# LED_STATUS.net
KiCad netlist of a schematic drawn in Altium Designer
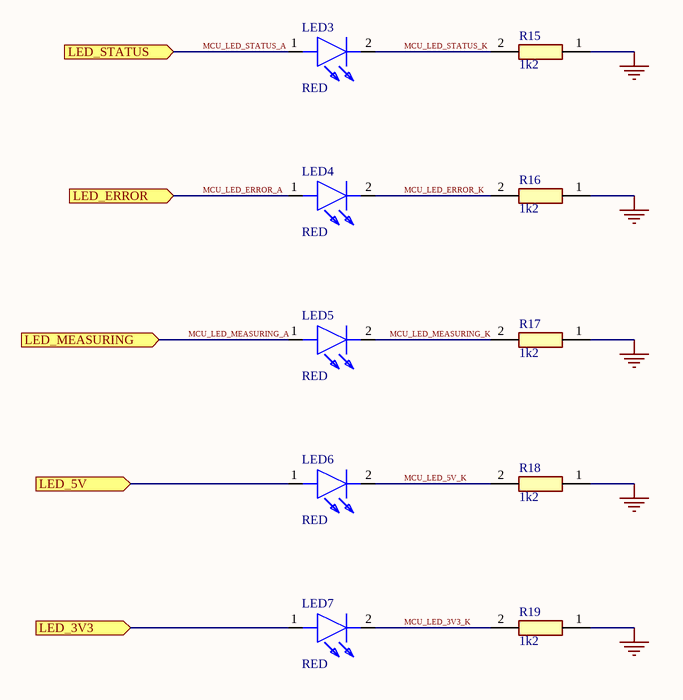
[diagram p0: LED_STATUS.SchDoc]

(export (version "E")
  (design (tool "Eeschema 10.0.6"))
  (components
    (comp (ref "LED3")
      (value "RED")
      (footprint "SamacSys:APT2012SECKJ3PRV")
      (description "LED")
      (fields
        (field (name "MANUFACTURER_PART_NUMBER") "APT2012SECK/J3-PRV")
        (field (name "MOUSER PART NUMBER") "604-APT2012SECKJ3PRV")
      )
      (libsource (lib "*") (part "APT2012SECK_J3-PRV"))
    )
    (comp (ref "LED4")
      (value "RED")
      (footprint "SamacSys:APT2012SECKJ3PRV")
      (description "LED")
      (fields
        (field (name "MANUFACTURER_PART_NUMBER") "APT2012SECK/J3-PRV")
        (field (name "MOUSER PART NUMBER") "604-APT2012SECKJ3PRV")
      )
      (libsource (lib "*") (part "APT2012SECK_J3-PRV"))
    )
    (comp (ref "LED5")
      (value "RED")
      (footprint "SamacSys:APT2012SECKJ3PRV")
      (description "LED")
      (fields
        (field (name "MANUFACTURER_PART_NUMBER") "APT2012SECK/J3-PRV")
        (field (name "MOUSER PART NUMBER") "604-APT2012SECKJ3PRV")
      )
      (libsource (lib "*") (part "APT2012SECK_J3-PRV"))
    )
    (comp (ref "LED6")
      (value "RED")
      (footprint "SamacSys:APT2012SECKJ3PRV")
      (description "LED")
      (fields
        (field (name "MANUFACTURER_PART_NUMBER") "APT2012SECK/J3-PRV")
        (field (name "MOUSER PART NUMBER") "604-APT2012SECKJ3PRV")
      )
      (libsource (lib "*") (part "APT2012SECK_J3-PRV"))
    )
    (comp (ref "LED7")
      (value "RED")
      (footprint "SamacSys:APT2012SECKJ3PRV")
      (description "LED")
      (fields
        (field (name "MANUFACTURER_PART_NUMBER") "APT2012SECK/J3-PRV")
        (field (name "MOUSER PART NUMBER") "604-APT2012SECKJ3PRV")
      )
      (libsource (lib "*") (part "APT2012SECK_J3-PRV"))
    )
    (comp (ref "R15")
      (value "1k2")
      (footprint "SamacSys:RESC1608X55N")
      (description "Resistor")
      (fields
        (field (name "MANUFACTURER_PART_NUMBER") "RK73B1JTTD103J")
        (field (name "MOUSER PART NUMBER") "660-RK73B1JTTD103J")
      )
      (libsource (lib "*") (part "RK73B1JTTD103J"))
    )
    (comp (ref "R16")
      (value "1k2")
      (footprint "SamacSys:RESC1608X55N")
      (description "Resistor")
      (fields
        (field (name "MANUFACTURER_PART_NUMBER") "RK73B1JTTD103J")
        (field (name "MOUSER PART NUMBER") "660-RK73B1JTTD103J")
      )
      (libsource (lib "*") (part "RK73B1JTTD103J"))
    )
    (comp (ref "R17")
      (value "1k2")
      (footprint "SamacSys:RESC1608X55N")
      (description "Resistor")
      (fields
        (field (name "MANUFACTURER_PART_NUMBER") "RK73B1JTTD103J")
        (field (name "MOUSER PART NUMBER") "660-RK73B1JTTD103J")
      )
      (libsource (lib "*") (part "RK73B1JTTD103J"))
    )
    (comp (ref "R18")
      (value "1k2")
      (footprint "SamacSys:RESC1608X55N")
      (description "Resistor")
      (fields
        (field (name "MANUFACTURER_PART_NUMBER") "RK73B1JTTD103J")
        (field (name "MOUSER PART NUMBER") "660-RK73B1JTTD103J")
      )
      (libsource (lib "*") (part "RK73B1JTTD103J"))
    )
    (comp (ref "R19")
      (value "1k2")
      (footprint "SamacSys:RESC1608X55N")
      (description "Resistor")
      (fields
        (field (name "MANUFACTURER_PART_NUMBER") "RK73B1JTTD103J")
        (field (name "MOUSER PART NUMBER") "660-RK73B1JTTD103J")
      )
      (libsource (lib "*") (part "RK73B1JTTD103J"))
    )
  )
  (nets
    (net (code "1") (name "/LED_3V3") (class "Default")
      (node (ref "LED7") (pin "1") (pinfunction "A_1") (pintype "passive"))
    )
    (net (code "2") (name "/LED_5V") (class "Default")
      (node (ref "LED6") (pin "1") (pinfunction "A_1") (pintype "passive"))
    )
    (net (code "3") (name "/MCU_LED_3V3_K") (class "Default")
      (node (ref "LED7") (pin "2") (pinfunction "K_2") (pintype "passive"))
      (node (ref "R19") (pin "2") (pinfunction "2_2") (pintype "passive"))
    )
    (net (code "4") (name "/MCU_LED_5V_K") (class "Default")
      (node (ref "LED6") (pin "2") (pinfunction "K_2") (pintype "passive"))
      (node (ref "R18") (pin "2") (pinfunction "2_2") (pintype "passive"))
    )
    (net (code "5") (name "/MCU_LED_ERROR_A") (class "Default")
      (node (ref "LED4") (pin "1") (pinfunction "A_1") (pintype "passive"))
    )
    (net (code "6") (name "/MCU_LED_ERROR_K") (class "Default")
      (node (ref "LED4") (pin "2") (pinfunction "K_2") (pintype "passive"))
      (node (ref "R16") (pin "2") (pinfunction "2_2") (pintype "passive"))
    )
    (net (code "7") (name "/MCU_LED_MEASURING_A") (class "Default")
      (node (ref "LED5") (pin "1") (pinfunction "A_1") (pintype "passive"))
    )
    (net (code "8") (name "/MCU_LED_MEASURING_K") (class "Default")
      (node (ref "LED5") (pin "2") (pinfunction "K_2") (pintype "passive"))
      (node (ref "R17") (pin "2") (pinfunction "2_2") (pintype "passive"))
    )
    (net (code "9") (name "/MCU_LED_STATUS_A") (class "Default")
      (node (ref "LED3") (pin "1") (pinfunction "A_1") (pintype "passive"))
    )
    (net (code "10") (name "/MCU_LED_STATUS_K") (class "Default")
      (node (ref "LED3") (pin "2") (pinfunction "K_2") (pintype "passive"))
      (node (ref "R15") (pin "2") (pinfunction "2_2") (pintype "passive"))
    )
    (net (code "11") (name "GND") (class "Default")
      (node (ref "R15") (pin "1") (pinfunction "1_1") (pintype "passive"))
      (node (ref "R16") (pin "1") (pinfunction "1_1") (pintype "passive"))
      (node (ref "R17") (pin "1") (pinfunction "1_1") (pintype "passive"))
      (node (ref "R18") (pin "1") (pinfunction "1_1") (pintype "passive"))
      (node (ref "R19") (pin "1") (pinfunction "1_1") (pintype "passive"))
    )
  )
)
